# motor_shield_v1.net
KiCad netlist of a schematic drawn in EAGLE
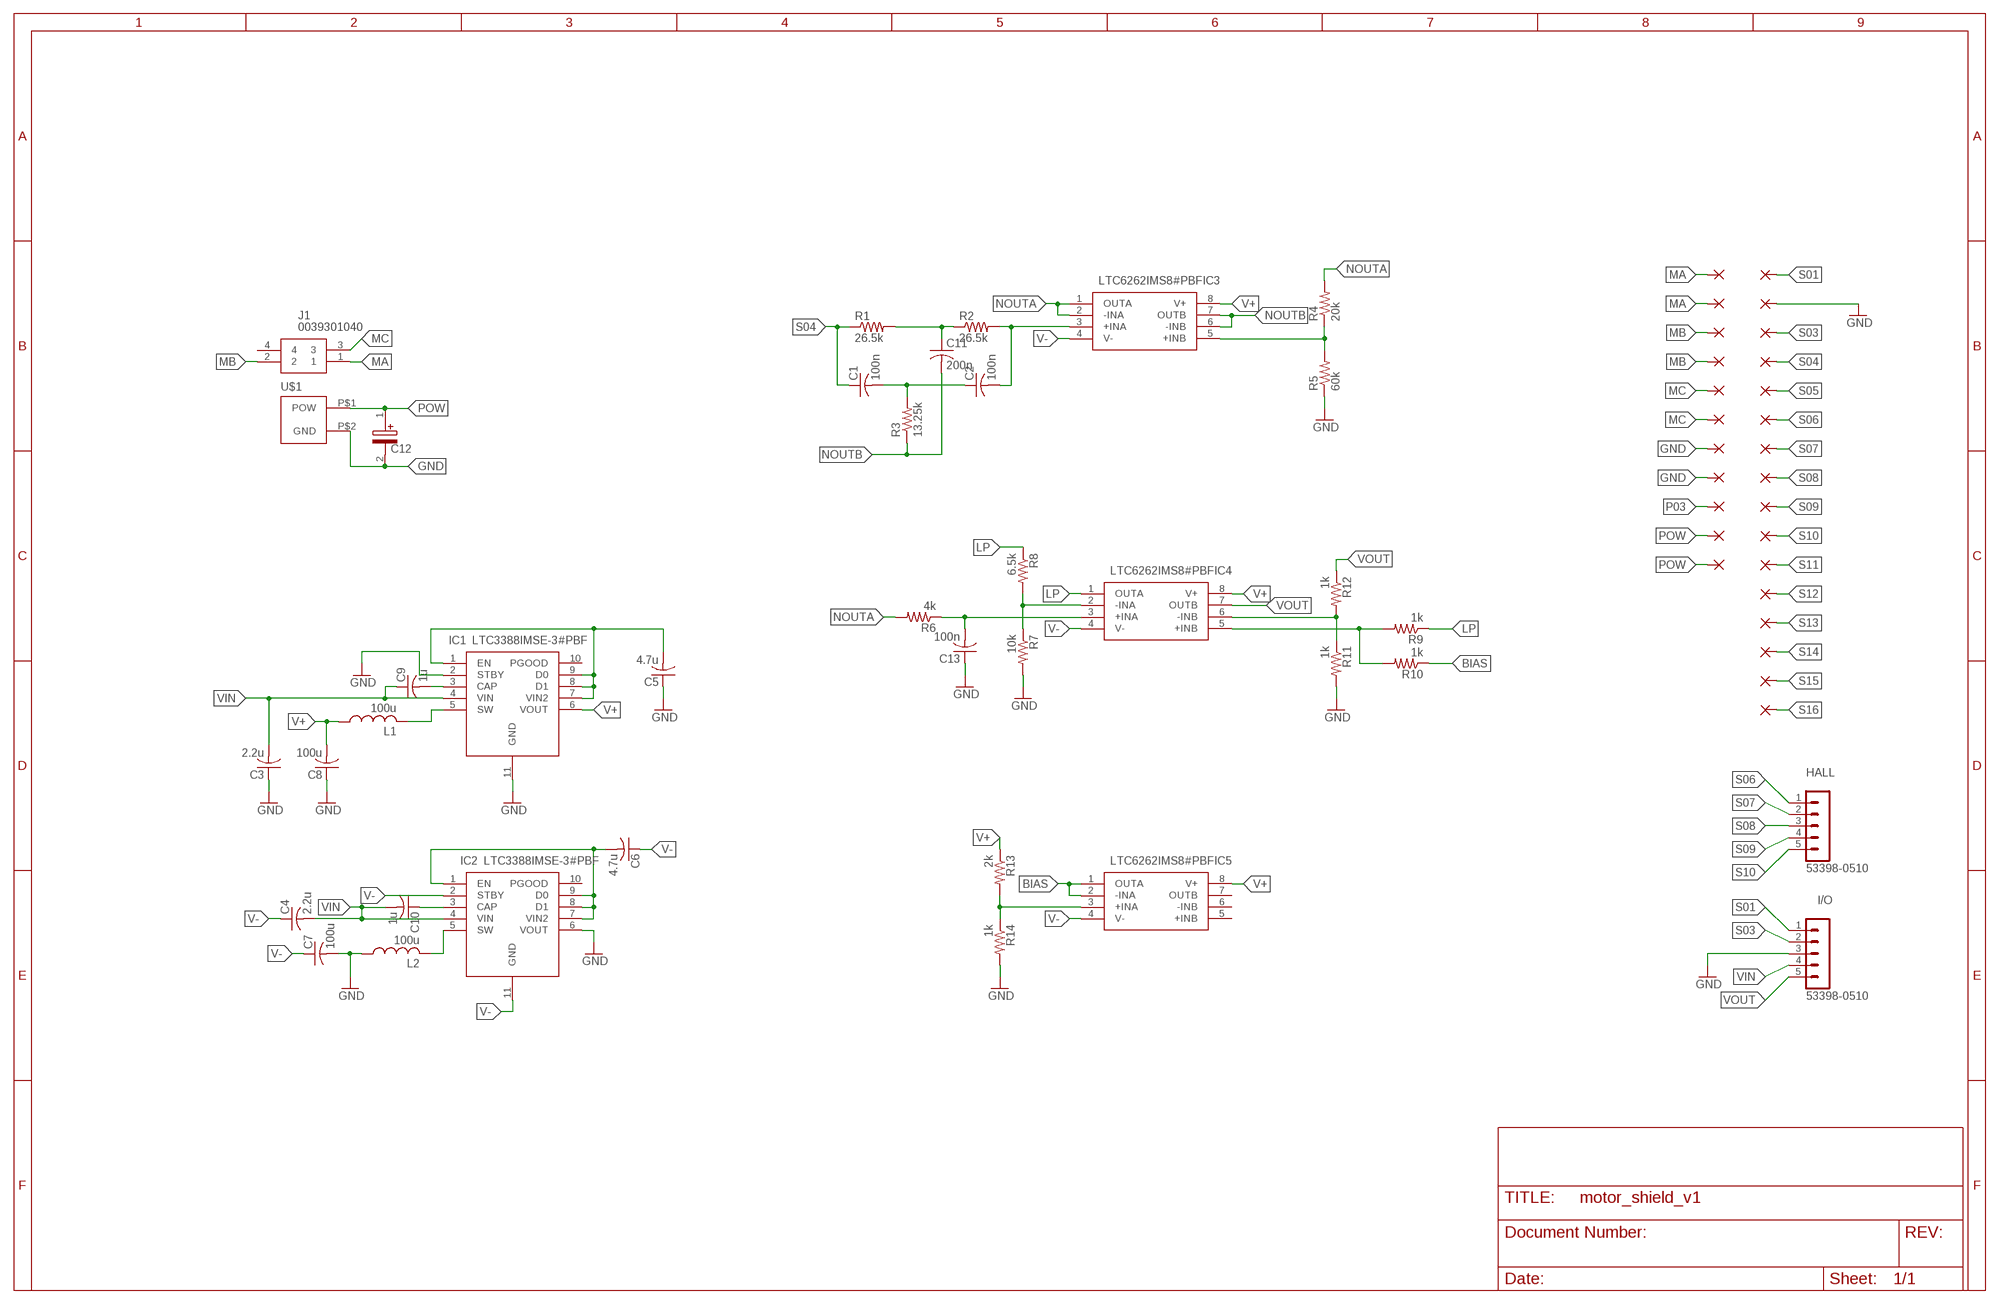
[diagram p0: schematic, sheet 1]

(export (version "E")
  (design (tool "Eeschema 10.0.6"))
  (components
    (comp (ref "C1")
      (value "100n")
      (footprint "eagle-import:C0805")
      (libsource (lib "eagle-import") (part "C-USC0805"))
    )
    (comp (ref "C2")
      (value "100n")
      (footprint "eagle-import:C0805")
      (libsource (lib "eagle-import") (part "C-USC0805"))
    )
    (comp (ref "C3")
      (value "2.2u")
      (footprint "eagle-import:C0805")
      (libsource (lib "eagle-import") (part "C-USC0805"))
    )
    (comp (ref "C4")
      (value "2.2u")
      (footprint "eagle-import:C0805")
      (libsource (lib "eagle-import") (part "C-USC0805"))
    )
    (comp (ref "C5")
      (value "4.7u")
      (footprint "eagle-import:C0805")
      (libsource (lib "eagle-import") (part "C-USC0805"))
    )
    (comp (ref "C6")
      (value "4.7u")
      (footprint "eagle-import:C0805")
      (libsource (lib "eagle-import") (part "C-USC0805"))
    )
    (comp (ref "C7")
      (value "100u")
      (footprint "eagle-import:C0805")
      (libsource (lib "eagle-import") (part "C-USC0805"))
    )
    (comp (ref "C8")
      (value "100u")
      (footprint "eagle-import:C0805")
      (libsource (lib "eagle-import") (part "C-USC0805"))
    )
    (comp (ref "C9")
      (value "1u")
      (footprint "eagle-import:C0805")
      (libsource (lib "eagle-import") (part "C-USC0805"))
    )
    (comp (ref "C10")
      (value "1u")
      (footprint "eagle-import:C0805")
      (libsource (lib "eagle-import") (part "C-USC0805"))
    )
    (comp (ref "C11")
      (value "200n")
      (footprint "eagle-import:C0805")
      (libsource (lib "eagle-import") (part "C-USC0805"))
    )
    (comp (ref "C12")
      (value "UVR2A101MPD")
      (footprint "eagle-import:CAPPRD500W60D1025H2200")
      (fields (field (name "MOUSER_PART_NUMBER") "647-UVR2A101MPD"))
      (libsource (lib "eagle-import") (part "UVR2A101MPD"))
    )
    (comp (ref "C13")
      (value "100n")
      (footprint "eagle-import:C0805")
      (libsource (lib "eagle-import") (part "C-USC0805"))
    )
    (comp (ref "HALL")
      (value "53398-0510")
      (footprint "eagle-import:53398-0510")
      (libsource (lib "eagle-import") (part "53398-0510"))
    )
    (comp (ref "I/O")
      (value "53398-0510")
      (footprint "eagle-import:53398-0510")
      (libsource (lib "eagle-import") (part "53398-0510"))
    )
    (comp (ref "IC1")
      (value "LTC3388IMSE-3#PBF")
      (footprint "eagle-import:SOP50P490X110-11N")
      (fields (field (name "MOUSER_PART_NUMBER") "584-LTC3388IMSE-3PBF"))
      (libsource (lib "eagle-import") (part "LTC3388IMSE-3#PBF"))
    )
    (comp (ref "IC2")
      (value "LTC3388IMSE-3#PBF")
      (footprint "eagle-import:SOP50P490X110-11N")
      (fields (field (name "MOUSER_PART_NUMBER") "584-LTC3388IMSE-3PBF"))
      (libsource (lib "eagle-import") (part "LTC3388IMSE-3#PBF"))
    )
    (comp (ref "IC3")
      (value "LTC6262IMS8#PBF")
      (footprint "eagle-import:SOP65P490X110-8N")
      (fields (field (name "MOUSER_PART_NUMBER") "584-LTC6262IMS8#PBF"))
      (libsource (lib "eagle-import") (part "LTC6262IMS8#PBF"))
    )
    (comp (ref "IC4")
      (value "LTC6262IMS8#PBF")
      (footprint "eagle-import:SOP65P490X110-8N")
      (fields (field (name "MOUSER_PART_NUMBER") "584-LTC6262IMS8#PBF"))
      (libsource (lib "eagle-import") (part "LTC6262IMS8#PBF"))
    )
    (comp (ref "IC5")
      (value "LTC6262IMS8#PBF")
      (footprint "eagle-import:SOP65P490X110-8N")
      (fields (field (name "MOUSER_PART_NUMBER") "584-LTC6262IMS8#PBF"))
      (libsource (lib "eagle-import") (part "LTC6262IMS8#PBF"))
    )
    (comp (ref "J1")
      (value "0039301040")
      (footprint "eagle-import:0039301040")
      (libsource (lib "eagle-import") (part "0039301040"))
    )
    (comp (ref "L1")
      (value "100u")
      (footprint "eagle-import:L2012C")
      (libsource (lib "eagle-import") (part "L-USL2012C"))
    )
    (comp (ref "L2")
      (value "100u")
      (footprint "eagle-import:L2012C")
      (libsource (lib "eagle-import") (part "L-USL2012C"))
    )
    (comp (ref "P01")
      (value "1,6/0,9")
      (footprint "eagle-import:1,6_0,9")
      (libsource (lib "eagle-import") (part "1,6/0,9"))
    )
    (comp (ref "P02")
      (value "1,6/0,9")
      (footprint "eagle-import:1,6_0,9")
      (libsource (lib "eagle-import") (part "1,6/0,9"))
    )
    (comp (ref "P03")
      (value "1,6/0,9")
      (footprint "eagle-import:1,6_0,9")
      (libsource (lib "eagle-import") (part "1,6/0,9"))
    )
    (comp (ref "P04")
      (value "1,6/0,9")
      (footprint "eagle-import:1,6_0,9")
      (libsource (lib "eagle-import") (part "1,6/0,9"))
    )
    (comp (ref "P05")
      (value "1,6/0,9")
      (footprint "eagle-import:1,6_0,9")
      (libsource (lib "eagle-import") (part "1,6/0,9"))
    )
    (comp (ref "P06")
      (value "1,6/0,9")
      (footprint "eagle-import:1,6_0,9")
      (libsource (lib "eagle-import") (part "1,6/0,9"))
    )
    (comp (ref "P07")
      (value "1,6/0,9")
      (footprint "eagle-import:1,6_0,9")
      (libsource (lib "eagle-import") (part "1,6/0,9"))
    )
    (comp (ref "P08")
      (value "1,6/0,9")
      (footprint "eagle-import:1,6_0,9")
      (libsource (lib "eagle-import") (part "1,6/0,9"))
    )
    (comp (ref "P09")
      (value "1,6/0,9")
      (footprint "eagle-import:1,6_0,9")
      (libsource (lib "eagle-import") (part "1,6/0,9"))
    )
    (comp (ref "P10")
      (value "1,6/0,9")
      (footprint "eagle-import:1,6_0,9")
      (libsource (lib "eagle-import") (part "1,6/0,9"))
    )
    (comp (ref "P11")
      (value "1,6/0,9")
      (footprint "eagle-import:1,6_0,9")
      (libsource (lib "eagle-import") (part "1,6/0,9"))
    )
    (comp (ref "R1")
      (value "26.5k")
      (footprint "eagle-import:R0805")
      (libsource (lib "eagle-import") (part "R-US_R0805"))
    )
    (comp (ref "R2")
      (value "26.5k")
      (footprint "eagle-import:R0805")
      (libsource (lib "eagle-import") (part "R-US_R0805"))
    )
    (comp (ref "R3")
      (value "13.25k")
      (footprint "eagle-import:R0805")
      (libsource (lib "eagle-import") (part "R-US_R0805"))
    )
    (comp (ref "R4")
      (value "20k")
      (footprint "eagle-import:R0805")
      (libsource (lib "eagle-import") (part "R-US_R0805"))
    )
    (comp (ref "R5")
      (value "60k")
      (footprint "eagle-import:R0805")
      (libsource (lib "eagle-import") (part "R-US_R0805"))
    )
    (comp (ref "R6")
      (value "4k")
      (footprint "eagle-import:R0805")
      (libsource (lib "eagle-import") (part "R-US_R0805"))
    )
    (comp (ref "R7")
      (value "10k")
      (footprint "eagle-import:R0805")
      (libsource (lib "eagle-import") (part "R-US_R0805"))
    )
    (comp (ref "R8")
      (value "6.5k")
      (footprint "eagle-import:R0805")
      (libsource (lib "eagle-import") (part "R-US_R0805"))
    )
    (comp (ref "R9")
      (value "1k")
      (footprint "eagle-import:R0805")
      (libsource (lib "eagle-import") (part "R-US_R0805"))
    )
    (comp (ref "R10")
      (value "1k")
      (footprint "eagle-import:R0805")
      (libsource (lib "eagle-import") (part "R-US_R0805"))
    )
    (comp (ref "R11")
      (value "1k")
      (footprint "eagle-import:R0805")
      (libsource (lib "eagle-import") (part "R-US_R0805"))
    )
    (comp (ref "R12")
      (value "1k")
      (footprint "eagle-import:R0805")
      (libsource (lib "eagle-import") (part "R-US_R0805"))
    )
    (comp (ref "R13")
      (value "2k")
      (footprint "eagle-import:R0805")
      (libsource (lib "eagle-import") (part "R-US_R0805"))
    )
    (comp (ref "R14")
      (value "1k")
      (footprint "eagle-import:R0805")
      (libsource (lib "eagle-import") (part "R-US_R0805"))
    )
    (comp (ref "S01")
      (value "1,6/0,9")
      (footprint "eagle-import:1,6_0,9")
      (libsource (lib "eagle-import") (part "1,6/0,9"))
    )
    (comp (ref "S02")
      (value "1,6/0,9")
      (footprint "eagle-import:1,6_0,9")
      (libsource (lib "eagle-import") (part "1,6/0,9"))
    )
    (comp (ref "S03")
      (value "1,6/0,9")
      (footprint "eagle-import:1,6_0,9")
      (libsource (lib "eagle-import") (part "1,6/0,9"))
    )
    (comp (ref "S04")
      (value "1,6/0,9")
      (footprint "eagle-import:1,6_0,9")
      (libsource (lib "eagle-import") (part "1,6/0,9"))
    )
    (comp (ref "S05")
      (value "1,6/0,9")
      (footprint "eagle-import:1,6_0,9")
      (libsource (lib "eagle-import") (part "1,6/0,9"))
    )
    (comp (ref "S06")
      (value "1,6/0,9")
      (footprint "eagle-import:1,6_0,9")
      (libsource (lib "eagle-import") (part "1,6/0,9"))
    )
    (comp (ref "S07")
      (value "1,6/0,9")
      (footprint "eagle-import:1,6_0,9")
      (libsource (lib "eagle-import") (part "1,6/0,9"))
    )
    (comp (ref "S08")
      (value "1,6/0,9")
      (footprint "eagle-import:1,6_0,9")
      (libsource (lib "eagle-import") (part "1,6/0,9"))
    )
    (comp (ref "S09")
      (value "1,6/0,9")
      (footprint "eagle-import:1,6_0,9")
      (libsource (lib "eagle-import") (part "1,6/0,9"))
    )
    (comp (ref "S10")
      (value "1,6/0,9")
      (footprint "eagle-import:1,6_0,9")
      (libsource (lib "eagle-import") (part "1,6/0,9"))
    )
    (comp (ref "S11")
      (value "1,6/0,9")
      (footprint "eagle-import:1,6_0,9")
      (libsource (lib "eagle-import") (part "1,6/0,9"))
    )
    (comp (ref "S12")
      (value "1,6/0,9")
      (footprint "eagle-import:1,6_0,9")
      (libsource (lib "eagle-import") (part "1,6/0,9"))
    )
    (comp (ref "S13")
      (value "1,6/0,9")
      (footprint "eagle-import:1,6_0,9")
      (libsource (lib "eagle-import") (part "1,6/0,9"))
    )
    (comp (ref "S14")
      (value "1,6/0,9")
      (footprint "eagle-import:1,6_0,9")
      (libsource (lib "eagle-import") (part "1,6/0,9"))
    )
    (comp (ref "S15")
      (value "1,6/0,9")
      (footprint "eagle-import:1,6_0,9")
      (libsource (lib "eagle-import") (part "1,6/0,9"))
    )
    (comp (ref "S16")
      (value "1,6/0,9")
      (footprint "eagle-import:1,6_0,9")
      (libsource (lib "eagle-import") (part "1,6/0,9"))
    )
    (comp (ref "U$1")
      (value "JR_2PM_DEV")
      (footprint "eagle-import:JR_2PM_B_FP")
      (libsource (lib "eagle-import") (part "JR_2PM_DEV"))
    )
  )
  (nets
    (net (code "1") (name "BIAS") (class "Default")
      (node (ref "IC5") (pin "1") (pinfunction "OUTA_1") (pintype "bidirectional"))
      (node (ref "IC5") (pin "2") (pinfunction "-INA_2") (pintype "bidirectional"))
      (node (ref "R10") (pin "1") (pinfunction "1_1") (pintype "passive"))
    )
    (net (code "2") (name "GND") (class "Default")
      (node (ref "C12") (pin "2") (pinfunction "-_2") (pintype "bidirectional"))
      (node (ref "C13") (pin "1") (pinfunction "1_1") (pintype "passive"))
      (node (ref "C3") (pin "1") (pinfunction "1_1") (pintype "passive"))
      (node (ref "C5") (pin "1") (pinfunction "1_1") (pintype "passive"))
      (node (ref "C7") (pin "2") (pinfunction "2_2") (pintype "passive"))
      (node (ref "C8") (pin "1") (pinfunction "1_1") (pintype "passive"))
      (node (ref "I/O") (pin "3") (pinfunction "3_3") (pintype "passive"))
      (node (ref "IC1") (pin "11") (pinfunction "GND_11") (pintype "bidirectional"))
      (node (ref "IC1") (pin "2") (pinfunction "STBY_2") (pintype "bidirectional"))
      (node (ref "IC2") (pin "6") (pinfunction "VOUT_6") (pintype "bidirectional"))
      (node (ref "L2") (pin "1") (pinfunction "1_1") (pintype "passive"))
      (node (ref "P07") (pin "1") (pinfunction "P_1") (pintype "passive"))
      (node (ref "P08") (pin "1") (pinfunction "P_1") (pintype "passive"))
      (node (ref "R11") (pin "2") (pinfunction "2_2") (pintype "passive"))
      (node (ref "R14") (pin "2") (pinfunction "2_2") (pintype "passive"))
      (node (ref "R5") (pin "1") (pinfunction "1_1") (pintype "passive"))
      (node (ref "R7") (pin "2") (pinfunction "2_2") (pintype "passive"))
      (node (ref "S02") (pin "1") (pinfunction "P_1") (pintype "passive"))
      (node (ref "U$1") (pin "P$2") (pinfunction "GND_P$2") (pintype "bidirectional"))
    )
    (net (code "3") (name "LP") (class "Default")
      (node (ref "IC4") (pin "1") (pinfunction "OUTA_1") (pintype "bidirectional"))
      (node (ref "R8") (pin "1") (pinfunction "1_1") (pintype "passive"))
      (node (ref "R9") (pin "1") (pinfunction "1_1") (pintype "passive"))
    )
    (net (code "4") (name "MA") (class "Default")
      (node (ref "J1") (pin "1") (pinfunction "1_1") (pintype "bidirectional"))
      (node (ref "P01") (pin "1") (pinfunction "P_1") (pintype "passive"))
      (node (ref "P02") (pin "1") (pinfunction "P_1") (pintype "passive"))
    )
    (net (code "5") (name "MB") (class "Default")
      (node (ref "J1") (pin "2") (pinfunction "2_2") (pintype "bidirectional"))
      (node (ref "P03") (pin "1") (pinfunction "P_1") (pintype "passive"))
      (node (ref "P04") (pin "1") (pinfunction "P_1") (pintype "passive"))
    )
    (net (code "6") (name "MC") (class "Default")
      (node (ref "J1") (pin "3") (pinfunction "3_3") (pintype "bidirectional"))
      (node (ref "P05") (pin "1") (pinfunction "P_1") (pintype "passive"))
      (node (ref "P06") (pin "1") (pinfunction "P_1") (pintype "passive"))
    )
    (net (code "7") (name "NOUTA") (class "Default")
      (node (ref "IC3") (pin "1") (pinfunction "OUTA_1") (pintype "bidirectional"))
      (node (ref "IC3") (pin "2") (pinfunction "-INA_2") (pintype "bidirectional"))
      (node (ref "R4") (pin "2") (pinfunction "2_2") (pintype "passive"))
      (node (ref "R6") (pin "2") (pinfunction "2_2") (pintype "passive"))
    )
    (net (code "8") (name "NOUTB") (class "Default")
      (node (ref "C11") (pin "2") (pinfunction "2_2") (pintype "passive"))
      (node (ref "IC3") (pin "6") (pinfunction "-INB_6") (pintype "bidirectional"))
      (node (ref "IC3") (pin "7") (pinfunction "OUTB_7") (pintype "bidirectional"))
      (node (ref "R3") (pin "1") (pinfunction "1_1") (pintype "passive"))
    )
    (net (code "9") (name "Net-(C1-Pad2)") (class "Default")
      (node (ref "C1") (pin "2") (pinfunction "2_2") (pintype "passive"))
      (node (ref "C2") (pin "1") (pinfunction "1_1") (pintype "passive"))
      (node (ref "R3") (pin "2") (pinfunction "2_2") (pintype "passive"))
    )
    (net (code "10") (name "Net-(C11-Pad1)") (class "Default")
      (node (ref "C11") (pin "1") (pinfunction "1_1") (pintype "passive"))
      (node (ref "R1") (pin "2") (pinfunction "2_2") (pintype "passive"))
      (node (ref "R2") (pin "1") (pinfunction "1_1") (pintype "passive"))
    )
    (net (code "11") (name "Net-(IC1-CAP)") (class "Default")
      (node (ref "C9") (pin "2") (pinfunction "2_2") (pintype "passive"))
      (node (ref "IC1") (pin "3") (pinfunction "CAP_3") (pintype "bidirectional"))
    )
    (net (code "12") (name "Net-(IC1-D0)") (class "Default")
      (node (ref "C5") (pin "2") (pinfunction "2_2") (pintype "passive"))
      (node (ref "IC1") (pin "1") (pinfunction "EN_1") (pintype "bidirectional"))
      (node (ref "IC1") (pin "7") (pinfunction "VIN2_7") (pintype "bidirectional"))
      (node (ref "IC1") (pin "8") (pinfunction "D1_8") (pintype "bidirectional"))
      (node (ref "IC1") (pin "9") (pinfunction "D0_9") (pintype "bidirectional"))
    )
    (net (code "13") (name "Net-(IC1-SW)") (class "Default")
      (node (ref "IC1") (pin "5") (pinfunction "SW_5") (pintype "bidirectional"))
      (node (ref "L1") (pin "2") (pinfunction "2_2") (pintype "passive"))
    )
    (net (code "14") (name "Net-(IC2-CAP)") (class "Default")
      (node (ref "C10") (pin "1") (pinfunction "1_1") (pintype "passive"))
      (node (ref "IC2") (pin "3") (pinfunction "CAP_3") (pintype "bidirectional"))
    )
    (net (code "15") (name "Net-(IC2-D0)") (class "Default")
      (node (ref "C6") (pin "2") (pinfunction "2_2") (pintype "passive"))
      (node (ref "IC2") (pin "1") (pinfunction "EN_1") (pintype "bidirectional"))
      (node (ref "IC2") (pin "7") (pinfunction "VIN2_7") (pintype "bidirectional"))
      (node (ref "IC2") (pin "8") (pinfunction "D1_8") (pintype "bidirectional"))
      (node (ref "IC2") (pin "9") (pinfunction "D0_9") (pintype "bidirectional"))
    )
    (net (code "16") (name "Net-(IC2-SW)") (class "Default")
      (node (ref "IC2") (pin "5") (pinfunction "SW_5") (pintype "bidirectional"))
      (node (ref "L2") (pin "2") (pinfunction "2_2") (pintype "passive"))
    )
    (net (code "17") (name "Net-(IC3-+INA)") (class "Default")
      (node (ref "C2") (pin "2") (pinfunction "2_2") (pintype "passive"))
      (node (ref "IC3") (pin "3") (pinfunction "+INA_3") (pintype "bidirectional"))
      (node (ref "R2") (pin "2") (pinfunction "2_2") (pintype "passive"))
    )
    (net (code "18") (name "Net-(IC3-+INB)") (class "Default")
      (node (ref "IC3") (pin "5") (pinfunction "+INB_5") (pintype "bidirectional"))
      (node (ref "R4") (pin "1") (pinfunction "1_1") (pintype "passive"))
      (node (ref "R5") (pin "2") (pinfunction "2_2") (pintype "passive"))
    )
    (net (code "19") (name "Net-(IC4-+INA)") (class "Default")
      (node (ref "C13") (pin "2") (pinfunction "2_2") (pintype "passive"))
      (node (ref "IC4") (pin "3") (pinfunction "+INA_3") (pintype "bidirectional"))
      (node (ref "R6") (pin "1") (pinfunction "1_1") (pintype "passive"))
    )
    (net (code "20") (name "Net-(IC4-+INB)") (class "Default")
      (node (ref "IC4") (pin "5") (pinfunction "+INB_5") (pintype "bidirectional"))
      (node (ref "R10") (pin "2") (pinfunction "2_2") (pintype "passive"))
      (node (ref "R9") (pin "2") (pinfunction "2_2") (pintype "passive"))
    )
    (net (code "21") (name "Net-(IC4--INA)") (class "Default")
      (node (ref "IC4") (pin "2") (pinfunction "-INA_2") (pintype "bidirectional"))
      (node (ref "R7") (pin "1") (pinfunction "1_1") (pintype "passive"))
      (node (ref "R8") (pin "2") (pinfunction "2_2") (pintype "passive"))
    )
    (net (code "22") (name "Net-(IC4--INB)") (class "Default")
      (node (ref "IC4") (pin "6") (pinfunction "-INB_6") (pintype "bidirectional"))
      (node (ref "R11") (pin "1") (pinfunction "1_1") (pintype "passive"))
      (node (ref "R12") (pin "2") (pinfunction "2_2") (pintype "passive"))
    )
    (net (code "23") (name "Net-(IC5-+INA)") (class "Default")
      (node (ref "IC5") (pin "3") (pinfunction "+INA_3") (pintype "bidirectional"))
      (node (ref "R13") (pin "2") (pinfunction "2_2") (pintype "passive"))
      (node (ref "R14") (pin "1") (pinfunction "1_1") (pintype "passive"))
    )
    (net (code "24") (name "P03") (class "Default")
      (node (ref "P09") (pin "1") (pinfunction "P_1") (pintype "passive"))
    )
    (net (code "25") (name "POW") (class "Default")
      (node (ref "C12") (pin "1") (pinfunction "+_1") (pintype "bidirectional"))
      (node (ref "P10") (pin "1") (pinfunction "P_1") (pintype "passive"))
      (node (ref "P11") (pin "1") (pinfunction "P_1") (pintype "passive"))
      (node (ref "U$1") (pin "P$1") (pinfunction "POW_P$1") (pintype "bidirectional"))
    )
    (net (code "26") (name "S01") (class "Default")
      (node (ref "I/O") (pin "1") (pinfunction "1_1") (pintype "passive"))
      (node (ref "S01") (pin "1") (pinfunction "P_1") (pintype "passive"))
    )
    (net (code "27") (name "S03") (class "Default")
      (node (ref "I/O") (pin "2") (pinfunction "2_2") (pintype "passive"))
      (node (ref "S03") (pin "1") (pinfunction "P_1") (pintype "passive"))
    )
    (net (code "28") (name "S04") (class "Default")
      (node (ref "C1") (pin "1") (pinfunction "1_1") (pintype "passive"))
      (node (ref "R1") (pin "1") (pinfunction "1_1") (pintype "passive"))
      (node (ref "S04") (pin "1") (pinfunction "P_1") (pintype "passive"))
    )
    (net (code "29") (name "S05") (class "Default")
      (node (ref "S05") (pin "1") (pinfunction "P_1") (pintype "passive"))
    )
    (net (code "30") (name "S06") (class "Default")
      (node (ref "HALL") (pin "1") (pinfunction "1_1") (pintype "passive"))
      (node (ref "S06") (pin "1") (pinfunction "P_1") (pintype "passive"))
    )
    (net (code "31") (name "S07") (class "Default")
      (node (ref "HALL") (pin "2") (pinfunction "2_2") (pintype "passive"))
      (node (ref "S07") (pin "1") (pinfunction "P_1") (pintype "passive"))
    )
    (net (code "32") (name "S08") (class "Default")
      (node (ref "HALL") (pin "3") (pinfunction "3_3") (pintype "passive"))
      (node (ref "S08") (pin "1") (pinfunction "P_1") (pintype "passive"))
    )
    (net (code "33") (name "S09") (class "Default")
      (node (ref "HALL") (pin "4") (pinfunction "4_4") (pintype "passive"))
      (node (ref "S09") (pin "1") (pinfunction "P_1") (pintype "passive"))
    )
    (net (code "34") (name "S10") (class "Default")
      (node (ref "HALL") (pin "5") (pinfunction "5_5") (pintype "passive"))
      (node (ref "S10") (pin "1") (pinfunction "P_1") (pintype "passive"))
    )
    (net (code "35") (name "S11") (class "Default")
      (node (ref "S11") (pin "1") (pinfunction "P_1") (pintype "passive"))
    )
    (net (code "36") (name "S12") (class "Default")
      (node (ref "S12") (pin "1") (pinfunction "P_1") (pintype "passive"))
    )
    (net (code "37") (name "S13") (class "Default")
      (node (ref "S13") (pin "1") (pinfunction "P_1") (pintype "passive"))
    )
    (net (code "38") (name "S14") (class "Default")
      (node (ref "S14") (pin "1") (pinfunction "P_1") (pintype "passive"))
    )
    (net (code "39") (name "S15") (class "Default")
      (node (ref "S15") (pin "1") (pinfunction "P_1") (pintype "passive"))
    )
    (net (code "40") (name "S16") (class "Default")
      (node (ref "S16") (pin "1") (pinfunction "P_1") (pintype "passive"))
    )
    (net (code "41") (name "V+") (class "Default")
      (node (ref "C8") (pin "2") (pinfunction "2_2") (pintype "passive"))
      (node (ref "IC1") (pin "6") (pinfunction "VOUT_6") (pintype "bidirectional"))
      (node (ref "IC3") (pin "8") (pinfunction "V+_8") (pintype "bidirectional"))
      (node (ref "IC4") (pin "8") (pinfunction "V+_8") (pintype "bidirectional"))
      (node (ref "IC5") (pin "8") (pinfunction "V+_8") (pintype "bidirectional"))
      (node (ref "L1") (pin "1") (pinfunction "1_1") (pintype "passive"))
      (node (ref "R13") (pin "1") (pinfunction "1_1") (pintype "passive"))
    )
    (net (code "42") (name "V-") (class "Default")
      (node (ref "C4") (pin "1") (pinfunction "1_1") (pintype "passive"))
      (node (ref "C6") (pin "1") (pinfunction "1_1") (pintype "passive"))
      (node (ref "C7") (pin "1") (pinfunction "1_1") (pintype "passive"))
      (node (ref "IC2") (pin "11") (pinfunction "GND_11") (pintype "bidirectional"))
      (node (ref "IC2") (pin "2") (pinfunction "STBY_2") (pintype "bidirectional"))
      (node (ref "IC3") (pin "4") (pinfunction "V-_4") (pintype "bidirectional"))
      (node (ref "IC4") (pin "4") (pinfunction "V-_4") (pintype "bidirectional"))
      (node (ref "IC5") (pin "4") (pinfunction "V-_4") (pintype "bidirectional"))
    )
    (net (code "43") (name "VIN") (class "Default")
      (node (ref "C10") (pin "2") (pinfunction "2_2") (pintype "passive"))
      (node (ref "C3") (pin "2") (pinfunction "2_2") (pintype "passive"))
      (node (ref "C4") (pin "2") (pinfunction "2_2") (pintype "passive"))
      (node (ref "C9") (pin "1") (pinfunction "1_1") (pintype "passive"))
      (node (ref "I/O") (pin "4") (pinfunction "4_4") (pintype "passive"))
      (node (ref "IC1") (pin "4") (pinfunction "VIN_4") (pintype "bidirectional"))
      (node (ref "IC2") (pin "4") (pinfunction "VIN_4") (pintype "bidirectional"))
    )
    (net (code "44") (name "VOUT") (class "Default")
      (node (ref "I/O") (pin "5") (pinfunction "5_5") (pintype "passive"))
      (node (ref "IC4") (pin "7") (pinfunction "OUTB_7") (pintype "bidirectional"))
      (node (ref "R12") (pin "1") (pinfunction "1_1") (pintype "passive"))
    )
    (net (code "45") (name "unconnected-(IC1-PGOOD-Pad10)") (class "Default")
      (node (ref "IC1") (pin "10") (pinfunction "PGOOD_10") (pintype "bidirectional"))
    )
    (net (code "46") (name "unconnected-(IC2-PGOOD-Pad10)") (class "Default")
      (node (ref "IC2") (pin "10") (pinfunction "PGOOD_10") (pintype "bidirectional"))
    )
    (net (code "47") (name "unconnected-(IC5-+INB-Pad5)") (class "Default")
      (node (ref "IC5") (pin "5") (pinfunction "+INB_5") (pintype "bidirectional"))
    )
    (net (code "48") (name "unconnected-(IC5--INB-Pad6)") (class "Default")
      (node (ref "IC5") (pin "6") (pinfunction "-INB_6") (pintype "bidirectional"))
    )
    (net (code "49") (name "unconnected-(IC5-OUTB-Pad7)") (class "Default")
      (node (ref "IC5") (pin "7") (pinfunction "OUTB_7") (pintype "bidirectional"))
    )
    (net (code "50") (name "unconnected-(J1-Pad4)") (class "Default")
      (node (ref "J1") (pin "4") (pinfunction "4_4") (pintype "bidirectional"))
    )
  )
)
